# ExpressCarduino.net
KiCad netlist of a schematic drawn in EAGLE
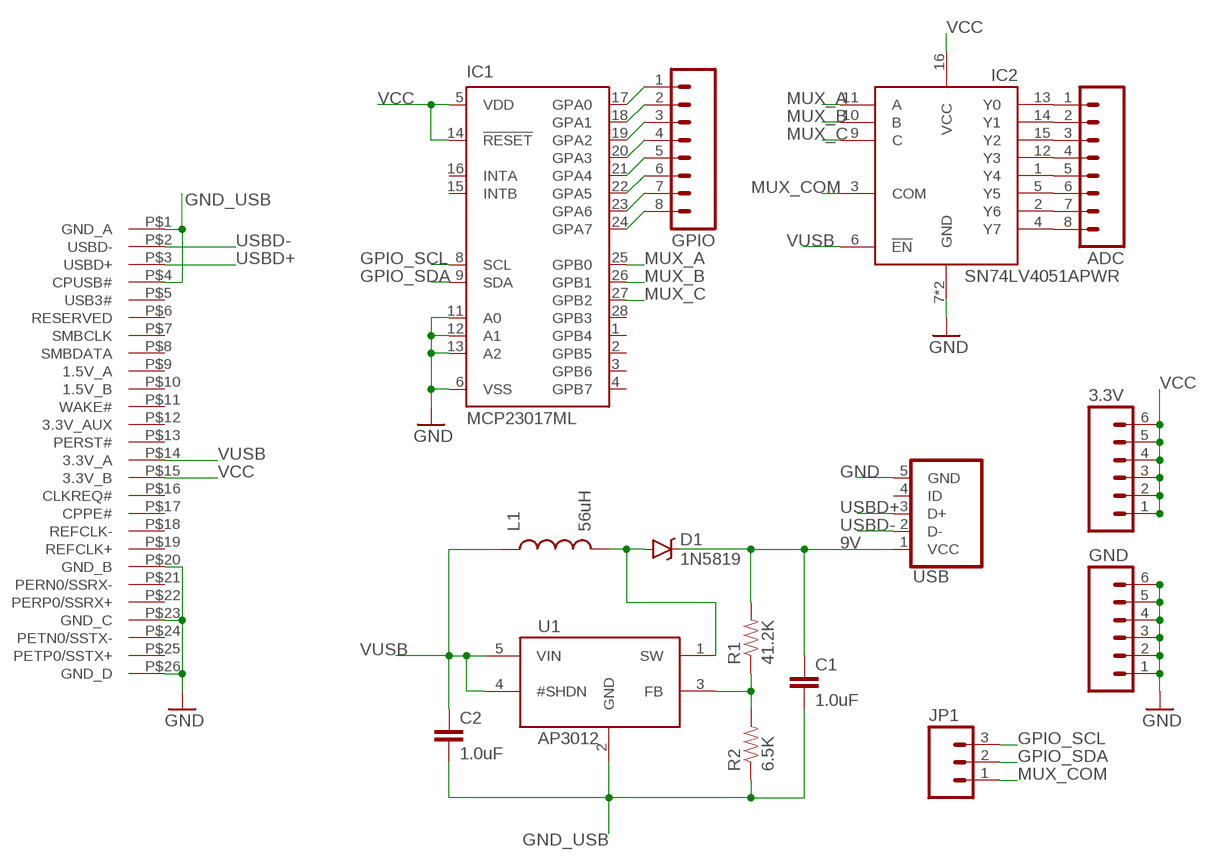
[diagram p0: schematic, sheet 1]

(export (version "E")
  (design (tool "Eeschema 10.0.6"))
  (components
    (comp (ref "3.3V")
      (value "M06SILK_FEMALE_PTH")
      (footprint "eagle-import:1X06")
      (libsource (lib "eagle-import") (part "M06SILK_FEMALE_PTH"))
    )
    (comp (ref "ADC")
      (value "M08")
      (footprint "eagle-import:1X08_ROUND")
      (libsource (lib "eagle-import") (part "M08"))
    )
    (comp (ref "C1")
      (value "1.0uF")
      (footprint "eagle-import:0603-CAP")
      (libsource (lib "eagle-import") (part "1.0UF-16V-10%(0603)"))
    )
    (comp (ref "C2")
      (value "1.0uF")
      (footprint "eagle-import:0603-CAP")
      (libsource (lib "eagle-import") (part "1.0UF-16V-10%(0603)"))
    )
    (comp (ref "D1")
      (value "1N5819")
      (footprint "eagle-import:SOD-123")
      (libsource (lib "eagle-import") (part "DIODE-SCHOTTKY"))
    )
    (comp (ref "GND")
      (value "M06SILK_FEMALE_PTH")
      (footprint "eagle-import:1X06")
      (libsource (lib "eagle-import") (part "M06SILK_FEMALE_PTH"))
    )
    (comp (ref "GPIO")
      (value "M08")
      (footprint "eagle-import:1X08_ROUND")
      (libsource (lib "eagle-import") (part "M08"))
    )
    (comp (ref "IC1")
      (value "MCP23017ML")
      (footprint "eagle-import:QFN28-ML_6X6MM")
      (libsource (lib "eagle-import") (part "MCP23017ML"))
    )
    (comp (ref "IC2")
      (value "SN74LV4051APWR")
      (footprint "eagle-import:TSSOP16")
      (libsource (lib "eagle-import") (part "SN74LV4051APWR"))
    )
    (comp (ref "JP1")
      (value "M03PTH")
      (footprint "eagle-import:1X03")
      (libsource (lib "eagle-import") (part "M03PTH"))
    )
    (comp (ref "L1")
      (value "56uH")
      (footprint "eagle-import:SDR0403")
      (libsource (lib "eagle-import") (part "INDUCTORSDR0403-560KL"))
    )
    (comp (ref "R1")
      (value "41.2K")
      (footprint "eagle-import:0805")
      (libsource (lib "eagle-import") (part "0.22OHM-1/4W-1%(0805)"))
    )
    (comp (ref "R2")
      (value "6.5K")
      (footprint "eagle-import:0805")
      (libsource (lib "eagle-import") (part "0.22OHM-1/4W-1%(0805)"))
    )
    (comp (ref "U$1")
      (value "EXPRESSCARD34")
      (footprint "eagle-import:EXPRESSCARD34")
      (libsource (lib "eagle-import") (part "EXPRESSCARD34"))
    )
    (comp (ref "U1")
      (value "AP3012")
      (footprint "eagle-import:SOT23-5")
      (libsource (lib "eagle-import") (part "AP3012"))
    )
    (comp (ref "USB")
      (value "USB_MICROB_PLUG\"")
      (footprint "eagle-import:MICRO-B-RA-SMT")
      (libsource (lib "eagle-import") (part "USB_MICROB_PLUG{dblquote}"))
    )
  )
  (nets
    (net (code "1") (name "/1.5V_A") (class "Default")
      (node (ref "U$1") (pin "P$9") (pinfunction "1.5V_A_P$9") (pintype "power_in"))
    )
    (net (code "2") (name "/1.5V_B") (class "Default")
      (node (ref "U$1") (pin "P$10") (pinfunction "1.5V_B_P$10") (pintype "power_in"))
    )
    (net (code "3") (name "/3.3V_AUX") (class "Default")
      (node (ref "U$1") (pin "P$12") (pinfunction "3.3V_AUX_P$12") (pintype "power_in"))
    )
    (net (code "4") (name "/9V") (class "Default")
      (node (ref "C1") (pin "1") (pinfunction "1_1") (pintype "passive"))
      (node (ref "D1") (pin "C") (pinfunction "C_C") (pintype "passive"))
      (node (ref "R1") (pin "2") (pinfunction "2_2") (pintype "passive"))
      (node (ref "USB") (pin "1") (pinfunction "VCC_1") (pintype "bidirectional"))
    )
    (net (code "5") (name "/GND_USB") (class "Default")
      (node (ref "C1") (pin "2") (pinfunction "2_2") (pintype "passive"))
      (node (ref "C2") (pin "2") (pinfunction "2_2") (pintype "passive"))
      (node (ref "R2") (pin "1") (pinfunction "1_1") (pintype "passive"))
      (node (ref "U$1") (pin "P$1") (pinfunction "GND_A_P$1") (pintype "power_in"))
      (node (ref "U$1") (pin "P$4") (pinfunction "CPUSB#_P$4") (pintype "input"))
      (node (ref "U1") (pin "2") (pinfunction "GND_2") (pintype "power_in"))
    )
    (net (code "6") (name "/GPIO_SCL") (class "Default")
      (node (ref "IC1") (pin "8") (pinfunction "SCL_8") (pintype "input"))
      (node (ref "JP1") (pin "3") (pinfunction "3_3") (pintype "passive"))
    )
    (net (code "7") (name "/GPIO_SDA") (class "Default")
      (node (ref "IC1") (pin "9") (pinfunction "SDA_9") (pintype "bidirectional"))
      (node (ref "JP1") (pin "2") (pinfunction "2_2") (pintype "passive"))
    )
    (net (code "8") (name "/MUX_A") (class "Default")
      (node (ref "IC1") (pin "25") (pinfunction "GPB0_25") (pintype "bidirectional"))
      (node (ref "IC2") (pin "11") (pinfunction "A_11") (pintype "input"))
    )
    (net (code "9") (name "/MUX_B") (class "Default")
      (node (ref "IC1") (pin "26") (pinfunction "GPB1_26") (pintype "bidirectional"))
      (node (ref "IC2") (pin "10") (pinfunction "B_10") (pintype "input"))
    )
    (net (code "10") (name "/MUX_C") (class "Default")
      (node (ref "IC1") (pin "27") (pinfunction "GPB2_27") (pintype "bidirectional"))
      (node (ref "IC2") (pin "9") (pinfunction "C_9") (pintype "input"))
    )
    (net (code "11") (name "/MUX_COM") (class "Default")
      (node (ref "IC2") (pin "3") (pinfunction "COM_3") (pintype "bidirectional"))
      (node (ref "JP1") (pin "1") (pinfunction "1_1") (pintype "passive"))
    )
    (net (code "12") (name "/USBD+") (class "Default")
      (node (ref "U$1") (pin "P$3") (pinfunction "USBD+_P$3") (pintype "bidirectional"))
      (node (ref "USB") (pin "3") (pinfunction "D+_3") (pintype "bidirectional"))
    )
    (net (code "13") (name "/USBD-") (class "Default")
      (node (ref "U$1") (pin "P$2") (pinfunction "USBD-_P$2") (pintype "bidirectional"))
      (node (ref "USB") (pin "2") (pinfunction "D-_2") (pintype "bidirectional"))
    )
    (net (code "14") (name "/VCC") (class "Default")
      (node (ref "3.3V") (pin "1") (pinfunction "1_1") (pintype "passive"))
      (node (ref "3.3V") (pin "2") (pinfunction "2_2") (pintype "passive"))
      (node (ref "3.3V") (pin "3") (pinfunction "3_3") (pintype "passive"))
      (node (ref "3.3V") (pin "4") (pinfunction "4_4") (pintype "passive"))
      (node (ref "3.3V") (pin "5") (pinfunction "5_5") (pintype "passive"))
      (node (ref "3.3V") (pin "6") (pinfunction "6_6") (pintype "passive"))
      (node (ref "IC1") (pin "14") (pinfunction "~{RESET}_14") (pintype "input"))
      (node (ref "IC1") (pin "5") (pinfunction "VDD_5") (pintype "power_in"))
      (node (ref "IC2") (pin "16") (pinfunction "VCC_16") (pintype "power_in"))
      (node (ref "U$1") (pin "P$15") (pinfunction "3.3V_B_P$15") (pintype "power_in"))
    )
    (net (code "15") (name "/VUSB") (class "Default")
      (node (ref "C2") (pin "1") (pinfunction "1_1") (pintype "passive"))
      (node (ref "IC2") (pin "6") (pinfunction "~{EN}_6") (pintype "input"))
      (node (ref "L1") (pin "P$1") (pinfunction "1_P$1") (pintype "passive"))
      (node (ref "U$1") (pin "P$14") (pinfunction "3.3V_A_P$14") (pintype "power_in"))
      (node (ref "U1") (pin "4") (pinfunction "#SHDN_4") (pintype "input"))
      (node (ref "U1") (pin "5") (pinfunction "VIN_5") (pintype "power_in"))
    )
    (net (code "16") (name "GND") (class "Default")
      (node (ref "GND") (pin "1") (pinfunction "1_1") (pintype "passive"))
      (node (ref "GND") (pin "2") (pinfunction "2_2") (pintype "passive"))
      (node (ref "GND") (pin "3") (pinfunction "3_3") (pintype "passive"))
      (node (ref "GND") (pin "4") (pinfunction "4_4") (pintype "passive"))
      (node (ref "GND") (pin "5") (pinfunction "5_5") (pintype "passive"))
      (node (ref "GND") (pin "6") (pinfunction "6_6") (pintype "passive"))
      (node (ref "IC1") (pin "11") (pinfunction "A0_11") (pintype "input"))
      (node (ref "IC1") (pin "12") (pinfunction "A1_12") (pintype "input"))
      (node (ref "IC1") (pin "13") (pinfunction "A2_13") (pintype "input"))
      (node (ref "IC1") (pin "6") (pinfunction "VSS_6") (pintype "power_in"))
      (node (ref "IC2") (pin "7") (pinfunction "GND_7") (pintype "power_in"))
      (node (ref "IC2") (pin "8") (pinfunction "GND_8") (pintype "power_in"))
      (node (ref "U$1") (pin "P$20") (pinfunction "GND_B_P$20") (pintype "power_in"))
      (node (ref "U$1") (pin "P$23") (pinfunction "GND_C_P$23") (pintype "power_in"))
      (node (ref "U$1") (pin "P$26") (pinfunction "GND_D_P$26") (pintype "power_in"))
      (node (ref "USB") (pin "5") (pinfunction "GND_5") (pintype "bidirectional"))
    )
    (net (code "17") (name "Net-(IC1-GPA0)") (class "Default")
      (node (ref "GPIO") (pin "1") (pinfunction "1_1") (pintype "passive"))
      (node (ref "IC1") (pin "17") (pinfunction "GPA0_17") (pintype "bidirectional"))
    )
    (net (code "18") (name "Net-(IC1-GPA1)") (class "Default")
      (node (ref "GPIO") (pin "2") (pinfunction "2_2") (pintype "passive"))
      (node (ref "IC1") (pin "18") (pinfunction "GPA1_18") (pintype "bidirectional"))
    )
    (net (code "19") (name "Net-(IC1-GPA2)") (class "Default")
      (node (ref "GPIO") (pin "3") (pinfunction "3_3") (pintype "passive"))
      (node (ref "IC1") (pin "19") (pinfunction "GPA2_19") (pintype "bidirectional"))
    )
    (net (code "20") (name "Net-(IC1-GPA3)") (class "Default")
      (node (ref "GPIO") (pin "4") (pinfunction "4_4") (pintype "passive"))
      (node (ref "IC1") (pin "20") (pinfunction "GPA3_20") (pintype "bidirectional"))
    )
    (net (code "21") (name "Net-(IC1-GPA4)") (class "Default")
      (node (ref "GPIO") (pin "5") (pinfunction "5_5") (pintype "passive"))
      (node (ref "IC1") (pin "21") (pinfunction "GPA4_21") (pintype "bidirectional"))
    )
    (net (code "22") (name "Net-(IC1-GPA5)") (class "Default")
      (node (ref "GPIO") (pin "6") (pinfunction "6_6") (pintype "passive"))
      (node (ref "IC1") (pin "22") (pinfunction "GPA5_22") (pintype "bidirectional"))
    )
    (net (code "23") (name "Net-(IC1-GPA6)") (class "Default")
      (node (ref "GPIO") (pin "7") (pinfunction "7_7") (pintype "passive"))
      (node (ref "IC1") (pin "23") (pinfunction "GPA6_23") (pintype "bidirectional"))
    )
    (net (code "24") (name "Net-(IC1-GPA7)") (class "Default")
      (node (ref "GPIO") (pin "8") (pinfunction "8_8") (pintype "passive"))
      (node (ref "IC1") (pin "24") (pinfunction "GPA7_24") (pintype "bidirectional"))
    )
    (net (code "25") (name "Net-(IC2-Y0)") (class "Default")
      (node (ref "ADC") (pin "1") (pinfunction "1_1") (pintype "passive"))
      (node (ref "IC2") (pin "13") (pinfunction "Y0_13") (pintype "bidirectional"))
    )
    (net (code "26") (name "Net-(IC2-Y1)") (class "Default")
      (node (ref "ADC") (pin "2") (pinfunction "2_2") (pintype "passive"))
      (node (ref "IC2") (pin "14") (pinfunction "Y1_14") (pintype "bidirectional"))
    )
    (net (code "27") (name "Net-(IC2-Y2)") (class "Default")
      (node (ref "ADC") (pin "3") (pinfunction "3_3") (pintype "passive"))
      (node (ref "IC2") (pin "15") (pinfunction "Y2_15") (pintype "bidirectional"))
    )
    (net (code "28") (name "Net-(IC2-Y3)") (class "Default")
      (node (ref "ADC") (pin "4") (pinfunction "4_4") (pintype "passive"))
      (node (ref "IC2") (pin "12") (pinfunction "Y3_12") (pintype "bidirectional"))
    )
    (net (code "29") (name "Net-(IC2-Y4)") (class "Default")
      (node (ref "ADC") (pin "5") (pinfunction "5_5") (pintype "passive"))
      (node (ref "IC2") (pin "1") (pinfunction "Y4_1") (pintype "bidirectional"))
    )
    (net (code "30") (name "Net-(IC2-Y5)") (class "Default")
      (node (ref "ADC") (pin "6") (pinfunction "6_6") (pintype "passive"))
      (node (ref "IC2") (pin "5") (pinfunction "Y5_5") (pintype "bidirectional"))
    )
    (net (code "31") (name "Net-(IC2-Y6)") (class "Default")
      (node (ref "ADC") (pin "7") (pinfunction "7_7") (pintype "passive"))
      (node (ref "IC2") (pin "2") (pinfunction "Y6_2") (pintype "bidirectional"))
    )
    (net (code "32") (name "Net-(IC2-Y7)") (class "Default")
      (node (ref "ADC") (pin "8") (pinfunction "8_8") (pintype "passive"))
      (node (ref "IC2") (pin "4") (pinfunction "Y7_4") (pintype "bidirectional"))
    )
    (net (code "33") (name "Net-(L1-2)") (class "Default")
      (node (ref "D1") (pin "A") (pinfunction "A_A") (pintype "passive"))
      (node (ref "L1") (pin "P$2") (pinfunction "2_P$2") (pintype "passive"))
      (node (ref "U1") (pin "1") (pinfunction "SW_1") (pintype "output"))
    )
    (net (code "34") (name "Net-(U1-FB)") (class "Default")
      (node (ref "R1") (pin "1") (pinfunction "1_1") (pintype "passive"))
      (node (ref "R2") (pin "2") (pinfunction "2_2") (pintype "passive"))
      (node (ref "U1") (pin "3") (pinfunction "FB_3") (pintype "input"))
    )
    (net (code "35") (name "unconnected-(IC1-GPB3-Pad28)") (class "Default")
      (node (ref "IC1") (pin "28") (pinfunction "GPB3_28") (pintype "bidirectional"))
    )
    (net (code "36") (name "unconnected-(IC1-GPB4-Pad1)") (class "Default")
      (node (ref "IC1") (pin "1") (pinfunction "GPB4_1") (pintype "bidirectional"))
    )
    (net (code "37") (name "unconnected-(IC1-GPB5-Pad2)") (class "Default")
      (node (ref "IC1") (pin "2") (pinfunction "GPB5_2") (pintype "bidirectional"))
    )
    (net (code "38") (name "unconnected-(IC1-GPB6-Pad3)") (class "Default")
      (node (ref "IC1") (pin "3") (pinfunction "GPB6_3") (pintype "bidirectional"))
    )
    (net (code "39") (name "unconnected-(IC1-GPB7-Pad4)") (class "Default")
      (node (ref "IC1") (pin "4") (pinfunction "GPB7_4") (pintype "bidirectional"))
    )
    (net (code "40") (name "unconnected-(IC1-INTA-Pad16)") (class "Default")
      (node (ref "IC1") (pin "16") (pinfunction "INTA_16") (pintype "output"))
    )
    (net (code "41") (name "unconnected-(IC1-INTB-Pad15)") (class "Default")
      (node (ref "IC1") (pin "15") (pinfunction "INTB_15") (pintype "output"))
    )
    (net (code "42") (name "unconnected-(U$1-CLKREQ#-PadP$16)") (class "Default")
      (node (ref "U$1") (pin "P$16") (pinfunction "CLKREQ#_P$16") (pintype "input"))
    )
    (net (code "43") (name "unconnected-(U$1-CPPE#-PadP$17)") (class "Default")
      (node (ref "U$1") (pin "P$17") (pinfunction "CPPE#_P$17") (pintype "input"))
    )
    (net (code "44") (name "unconnected-(U$1-PERN0{slash}SSRX--PadP$21)") (class "Default")
      (node (ref "U$1") (pin "P$21") (pinfunction "PERN0/SSRX-_P$21") (pintype "input"))
    )
    (net (code "45") (name "unconnected-(U$1-PERP0{slash}SSRX+-PadP$22)") (class "Default")
      (node (ref "U$1") (pin "P$22") (pinfunction "PERP0/SSRX+_P$22") (pintype "input"))
    )
    (net (code "46") (name "unconnected-(U$1-PERST#-PadP$13)") (class "Default")
      (node (ref "U$1") (pin "P$13") (pinfunction "PERST#_P$13") (pintype "output"))
    )
    (net (code "47") (name "unconnected-(U$1-PETN0{slash}SSTX--PadP$24)") (class "Default")
      (node (ref "U$1") (pin "P$24") (pinfunction "PETN0/SSTX-_P$24") (pintype "output"))
    )
    (net (code "48") (name "unconnected-(U$1-PETP0{slash}SSTX+-PadP$25)") (class "Default")
      (node (ref "U$1") (pin "P$25") (pinfunction "PETP0/SSTX+_P$25") (pintype "output"))
    )
    (net (code "49") (name "unconnected-(U$1-REFCLK+-PadP$19)") (class "Default")
      (node (ref "U$1") (pin "P$19") (pinfunction "REFCLK+_P$19") (pintype "output"))
    )
    (net (code "50") (name "unconnected-(U$1-REFCLK--PadP$18)") (class "Default")
      (node (ref "U$1") (pin "P$18") (pinfunction "REFCLK-_P$18") (pintype "output"))
    )
    (net (code "51") (name "unconnected-(U$1-RESERVED-PadP$6)") (class "Default")
      (node (ref "U$1") (pin "P$6") (pinfunction "RESERVED_P$6") (pintype "no_connect"))
    )
    (net (code "52") (name "unconnected-(U$1-SMBCLK-PadP$7)") (class "Default")
      (node (ref "U$1") (pin "P$7") (pinfunction "SMBCLK_P$7") (pintype "bidirectional"))
    )
    (net (code "53") (name "unconnected-(U$1-SMBDATA-PadP$8)") (class "Default")
      (node (ref "U$1") (pin "P$8") (pinfunction "SMBDATA_P$8") (pintype "bidirectional"))
    )
    (net (code "54") (name "unconnected-(U$1-USB3#-PadP$5)") (class "Default")
      (node (ref "U$1") (pin "P$5") (pinfunction "USB3#_P$5") (pintype "input"))
    )
    (net (code "55") (name "unconnected-(U$1-WAKE#-PadP$11)") (class "Default")
      (node (ref "U$1") (pin "P$11") (pinfunction "WAKE#_P$11") (pintype "input"))
    )
    (net (code "56") (name "unconnected-(USB-ID-Pad4)") (class "Default")
      (node (ref "USB") (pin "4") (pinfunction "ID_4") (pintype "bidirectional"))
    )
  )
)
